# Witch.net
KiCad netlist of a schematic drawn in EAGLE
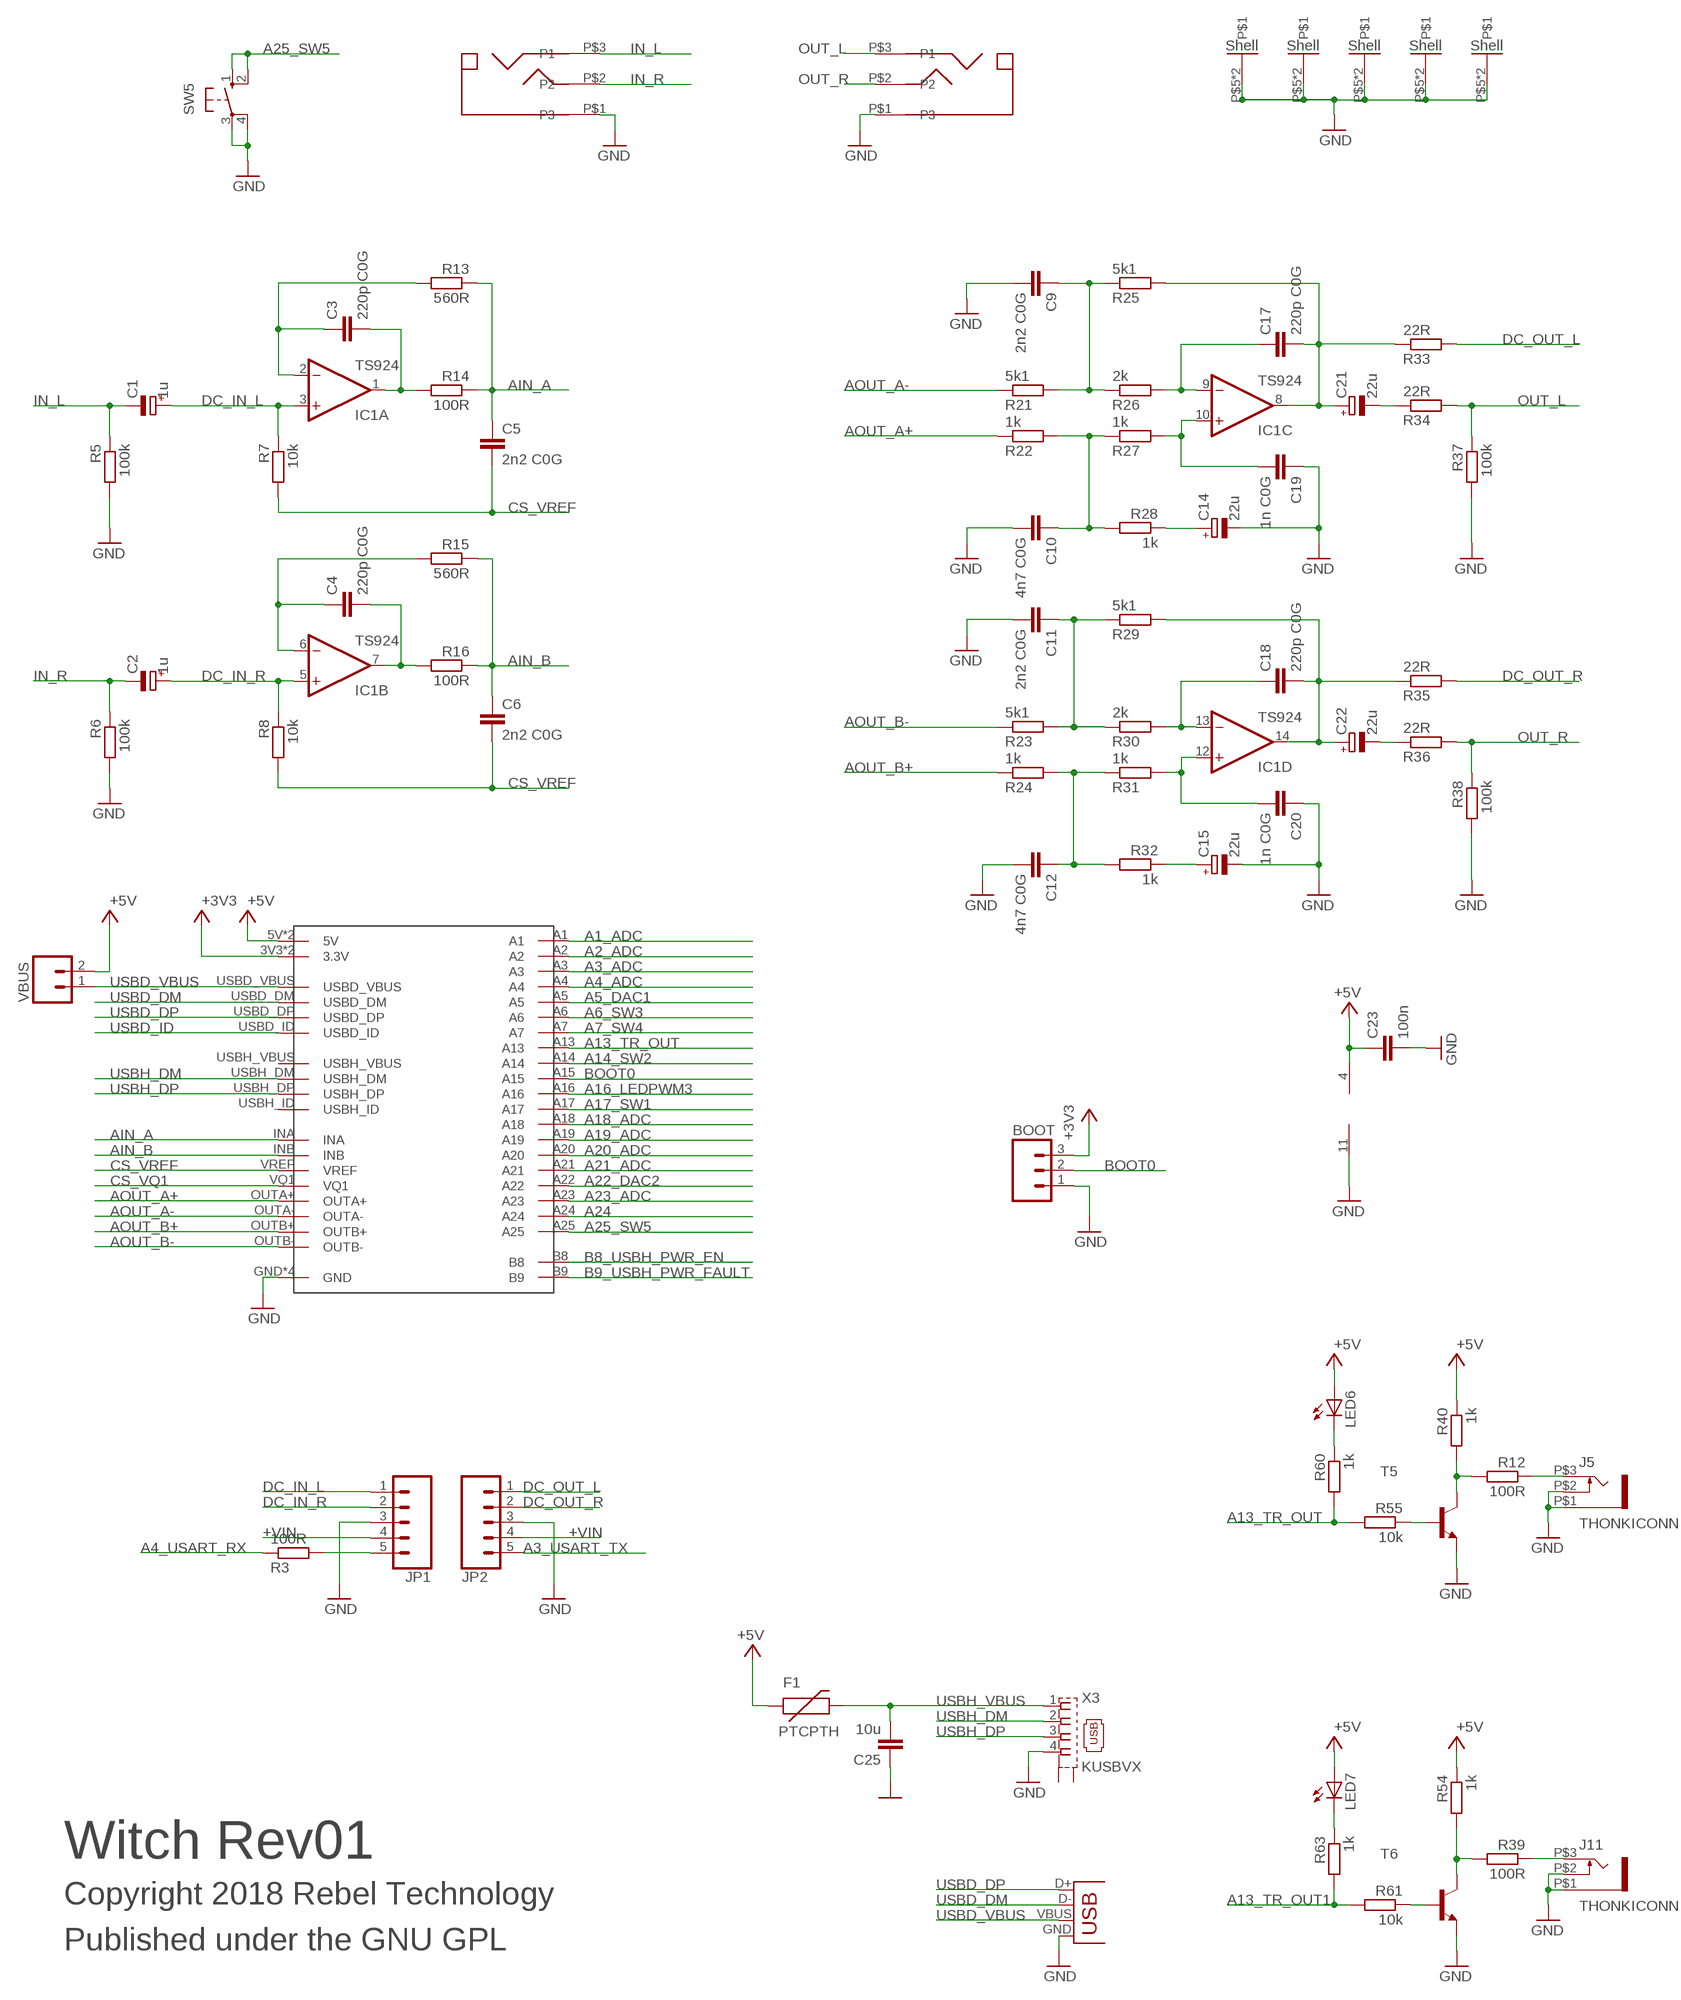
[diagram p0: schematic, sheet 1, part 1 of 2]
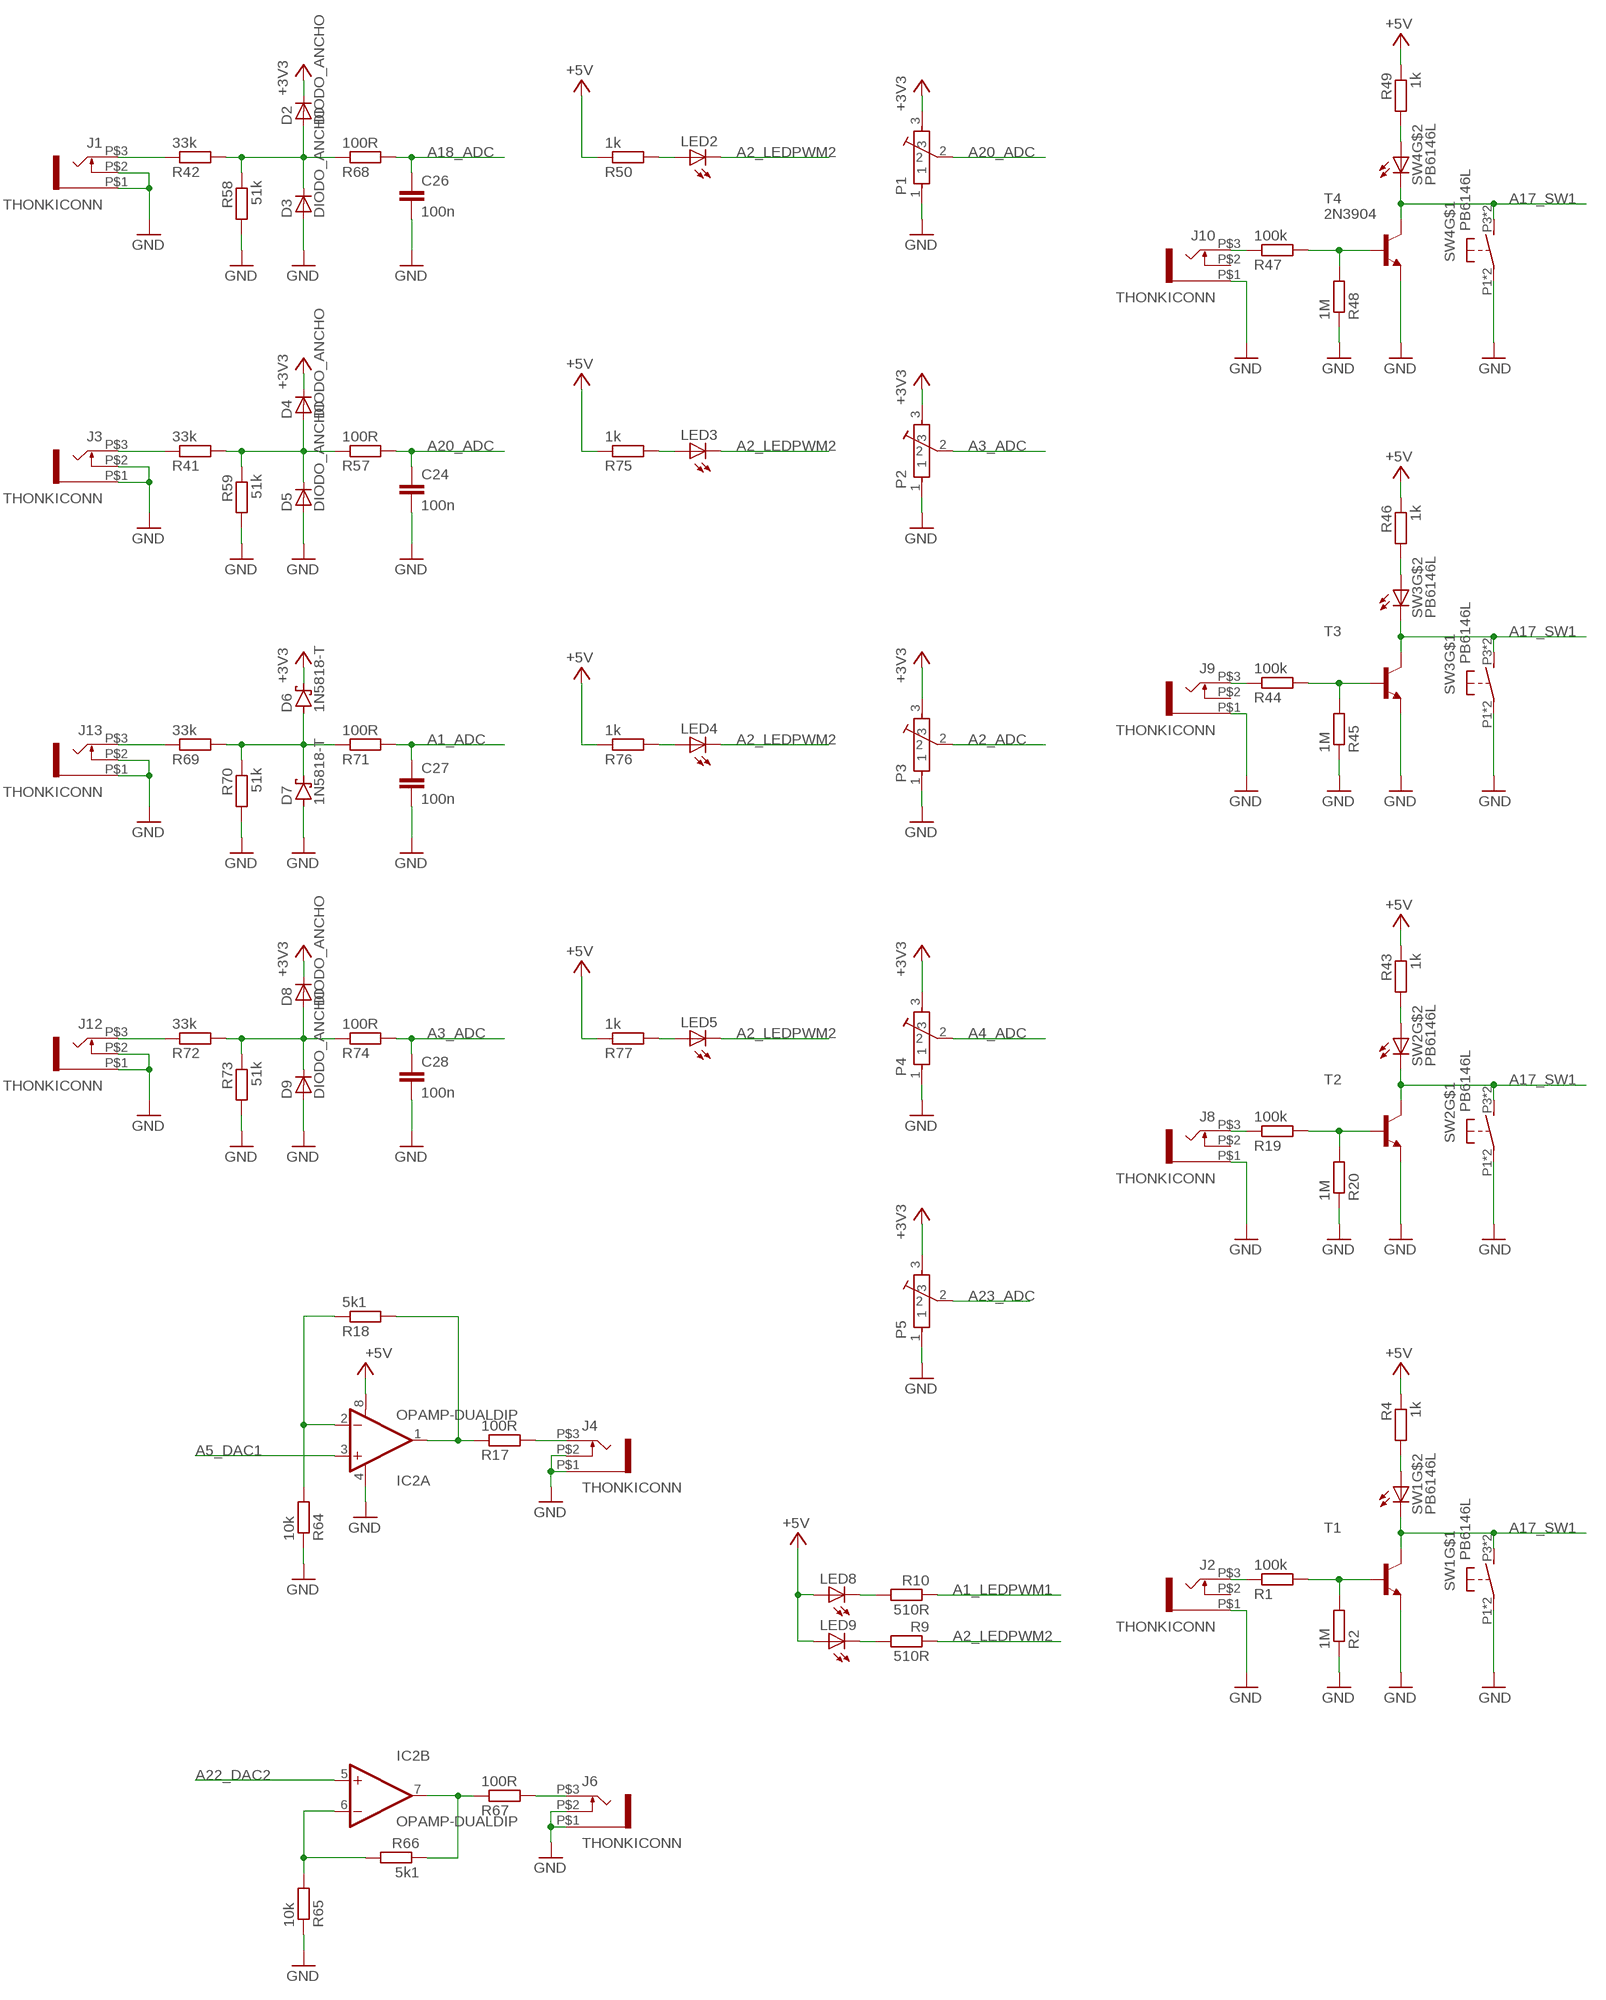
[diagram p1: schematic, sheet 1, part 2 of 2]

(export (version "E")
  (design (tool "Eeschema 10.0.6"))
  (components
    (comp (ref "BOOT")
      (value "M03PTH")
      (footprint "eagle-import:1X03")
      (libsource (lib "eagle-import") (part "M03PTH"))
    )
    (comp (ref "C1")
      (value "1u")
      (footprint "eagle-import:E1,8-4")
      (libsource (lib "eagle-import") (part "CPOL-EUE1.8-4"))
    )
    (comp (ref "C2")
      (value "1u")
      (footprint "eagle-import:E1,8-4")
      (libsource (lib "eagle-import") (part "CPOL-EUE1.8-4"))
    )
    (comp (ref "C3")
      (value "220p C0G")
      (footprint "eagle-import:C050-025X075")
      (libsource (lib "eagle-import") (part "C-EU050-025X075"))
    )
    (comp (ref "C4")
      (value "220p C0G")
      (footprint "eagle-import:C050-025X075")
      (libsource (lib "eagle-import") (part "C-EU050-025X075"))
    )
    (comp (ref "C5")
      (value "2n2 C0G")
      (footprint "eagle-import:C050-025X075")
      (libsource (lib "eagle-import") (part "C-EU050-025X075"))
    )
    (comp (ref "C6")
      (value "2n2 C0G")
      (footprint "eagle-import:C050-025X075")
      (libsource (lib "eagle-import") (part "C-EU050-025X075"))
    )
    (comp (ref "C9")
      (value "2n2 C0G")
      (footprint "eagle-import:C050-025X075")
      (libsource (lib "eagle-import") (part "C-EU050-025X075"))
    )
    (comp (ref "C10")
      (value "4n7 C0G")
      (footprint "eagle-import:C050-025X075")
      (libsource (lib "eagle-import") (part "C-EU050-025X075"))
    )
    (comp (ref "C11")
      (value "2n2 C0G")
      (footprint "eagle-import:C050-025X075")
      (libsource (lib "eagle-import") (part "C-EU050-025X075"))
    )
    (comp (ref "C12")
      (value "4n7 C0G")
      (footprint "eagle-import:C050-025X075")
      (libsource (lib "eagle-import") (part "C-EU050-025X075"))
    )
    (comp (ref "C14")
      (value "22u")
      (footprint "eagle-import:E1,8-4")
      (libsource (lib "eagle-import") (part "CPOL-EUE1.8-4"))
    )
    (comp (ref "C15")
      (value "22u")
      (footprint "eagle-import:E1,8-4")
      (libsource (lib "eagle-import") (part "CPOL-EUE1.8-4"))
    )
    (comp (ref "C17")
      (value "220p C0G")
      (footprint "eagle-import:C050-025X075")
      (libsource (lib "eagle-import") (part "C-EU050-025X075"))
    )
    (comp (ref "C18")
      (value "220p C0G")
      (footprint "eagle-import:C050-025X075")
      (libsource (lib "eagle-import") (part "C-EU050-025X075"))
    )
    (comp (ref "C19")
      (value "1n C0G")
      (footprint "eagle-import:C050-025X075")
      (libsource (lib "eagle-import") (part "C-EU050-025X075"))
    )
    (comp (ref "C20")
      (value "1n C0G")
      (footprint "eagle-import:C050-025X075")
      (libsource (lib "eagle-import") (part "C-EU050-025X075"))
    )
    (comp (ref "C21")
      (value "22u")
      (footprint "eagle-import:E1,8-4")
      (libsource (lib "eagle-import") (part "CPOL-EUE1.8-4"))
    )
    (comp (ref "C22")
      (value "22u")
      (footprint "eagle-import:E1,8-4")
      (libsource (lib "eagle-import") (part "CPOL-EUE1.8-4"))
    )
    (comp (ref "C23")
      (value "100n")
      (footprint "eagle-import:C050-025X075")
      (libsource (lib "eagle-import") (part "C-EU050-025X075"))
    )
    (comp (ref "C24")
      (value "100n")
      (footprint "eagle-import:C050-025X075")
      (libsource (lib "eagle-import") (part "C-EU050-025X075"))
    )
    (comp (ref "C25")
      (value "10u")
      (footprint "eagle-import:C050-025X075")
      (libsource (lib "eagle-import") (part "C-EU050-025X075"))
    )
    (comp (ref "C26")
      (value "100n")
      (footprint "eagle-import:C050-025X075")
      (libsource (lib "eagle-import") (part "C-EU050-025X075"))
    )
    (comp (ref "C27")
      (value "100n")
      (footprint "eagle-import:C050-025X075")
      (libsource (lib "eagle-import") (part "C-EU050-025X075"))
    )
    (comp (ref "C28")
      (value "100n")
      (footprint "eagle-import:C050-025X075")
      (libsource (lib "eagle-import") (part "C-EU050-025X075"))
    )
    (comp (ref "D2")
      (value "DIODO_ANCHO")
      (footprint "eagle-import:D-5.2")
      (libsource (lib "eagle-import") (part "DIODO_ANCHO"))
    )
    (comp (ref "D3")
      (value "DIODO_ANCHO")
      (footprint "eagle-import:D-5.2")
      (libsource (lib "eagle-import") (part "DIODO_ANCHO"))
    )
    (comp (ref "D4")
      (value "DIODO_ANCHO")
      (footprint "eagle-import:D-5.2")
      (libsource (lib "eagle-import") (part "DIODO_ANCHO"))
    )
    (comp (ref "D5")
      (value "DIODO_ANCHO")
      (footprint "eagle-import:D-5.2")
      (libsource (lib "eagle-import") (part "DIODO_ANCHO"))
    )
    (comp (ref "D6")
      (value "1N5818-T")
      (footprint "eagle-import:DO41-7.6")
      (libsource (lib "eagle-import") (part "1N5818-T"))
    )
    (comp (ref "D7")
      (value "1N5818-T")
      (footprint "eagle-import:DO41-7.6")
      (libsource (lib "eagle-import") (part "1N5818-T"))
    )
    (comp (ref "D8")
      (value "DIODO_ANCHO")
      (footprint "eagle-import:D-5.2")
      (libsource (lib "eagle-import") (part "DIODO_ANCHO"))
    )
    (comp (ref "D9")
      (value "DIODO_ANCHO")
      (footprint "eagle-import:D-5.2")
      (libsource (lib "eagle-import") (part "DIODO_ANCHO"))
    )
    (comp (ref "F1")
      (value "PTCPTH")
      (footprint "eagle-import:PTC")
      (libsource (lib "eagle-import") (part "PTCPTH"))
    )
    (comp (ref "IC1")
      (value "TS924")
      (footprint "eagle-import:DIL14")
      (libsource (lib "eagle-import") (part "LM324N"))
    )
    (comp (ref "IC2")
      (value "OPAMP-DUALDIP")
      (footprint "eagle-import:DIP08")
      (libsource (lib "eagle-import") (part "OPAMP-DUALDIP"))
    )
    (comp (ref "J1")
      (value "THONKICONN")
      (footprint "eagle-import:THONKICONN")
      (libsource (lib "eagle-import") (part "THONKICONN"))
    )
    (comp (ref "J2")
      (value "THONKICONN")
      (footprint "eagle-import:THONKICONN")
      (libsource (lib "eagle-import") (part "THONKICONN"))
    )
    (comp (ref "J3")
      (value "THONKICONN")
      (footprint "eagle-import:THONKICONN")
      (libsource (lib "eagle-import") (part "THONKICONN"))
    )
    (comp (ref "J4")
      (value "THONKICONN")
      (footprint "eagle-import:THONKICONN")
      (libsource (lib "eagle-import") (part "THONKICONN"))
    )
    (comp (ref "J5")
      (value "THONKICONN")
      (footprint "eagle-import:THONKICONN")
      (libsource (lib "eagle-import") (part "THONKICONN"))
    )
    (comp (ref "J6")
      (value "THONKICONN")
      (footprint "eagle-import:THONKICONN")
      (libsource (lib "eagle-import") (part "THONKICONN"))
    )
    (comp (ref "J8")
      (value "THONKICONN")
      (footprint "eagle-import:THONKICONN")
      (libsource (lib "eagle-import") (part "THONKICONN"))
    )
    (comp (ref "J9")
      (value "THONKICONN")
      (footprint "eagle-import:THONKICONN")
      (libsource (lib "eagle-import") (part "THONKICONN"))
    )
    (comp (ref "J10")
      (value "THONKICONN")
      (footprint "eagle-import:THONKICONN")
      (libsource (lib "eagle-import") (part "THONKICONN"))
    )
    (comp (ref "J11")
      (value "THONKICONN")
      (footprint "eagle-import:THONKICONN")
      (libsource (lib "eagle-import") (part "THONKICONN"))
    )
    (comp (ref "J12")
      (value "THONKICONN")
      (footprint "eagle-import:THONKICONN")
      (libsource (lib "eagle-import") (part "THONKICONN"))
    )
    (comp (ref "J13")
      (value "THONKICONN")
      (footprint "eagle-import:THONKICONN")
      (libsource (lib "eagle-import") (part "THONKICONN"))
    )
    (comp (ref "JP1")
      (value "CONN_05JST-VERT")
      (footprint "eagle-import:JST-5-PTH-VERT")
      (libsource (lib "eagle-import") (part "CONN_05JST-VERT"))
    )
    (comp (ref "JP2")
      (value "CONN_05JST-VERT")
      (footprint "eagle-import:JST-5-PTH-VERT")
      (libsource (lib "eagle-import") (part "CONN_05JST-VERT"))
    )
    (comp (ref "LED2")
      (value "LED3MM")
      (footprint "eagle-import:LED3MM")
      (libsource (lib "eagle-import") (part "LED3MM"))
    )
    (comp (ref "LED3")
      (value "LED3MM")
      (footprint "eagle-import:LED3MM")
      (libsource (lib "eagle-import") (part "LED3MM"))
    )
    (comp (ref "LED4")
      (value "LED3MM")
      (footprint "eagle-import:LED3MM")
      (libsource (lib "eagle-import") (part "LED3MM"))
    )
    (comp (ref "LED5")
      (value "LED3MM")
      (footprint "eagle-import:LED3MM")
      (libsource (lib "eagle-import") (part "LED3MM"))
    )
    (comp (ref "LED6")
      (value "LED3MM")
      (footprint "eagle-import:LED3MM")
      (libsource (lib "eagle-import") (part "LED3MM"))
    )
    (comp (ref "LED7")
      (value "LED3MM")
      (footprint "eagle-import:LED3MM")
      (libsource (lib "eagle-import") (part "LED3MM"))
    )
    (comp (ref "LED8")
      (value "LED3MM")
      (footprint "eagle-import:LED3MM")
      (libsource (lib "eagle-import") (part "LED3MM"))
    )
    (comp (ref "LED9")
      (value "LED3MM")
      (footprint "eagle-import:LED3MM")
      (libsource (lib "eagle-import") (part "LED3MM"))
    )
    (comp (ref "P1")
      (value "POT-ALPS-RK09L1140")
      (footprint "eagle-import:POT-ALPS-RK09L1140")
      (libsource (lib "eagle-import") (part "POT-ALPS-RK09L1140"))
    )
    (comp (ref "P2")
      (value "POT-ALPS-RK09L1140")
      (footprint "eagle-import:POT-ALPS-RK09L1140")
      (libsource (lib "eagle-import") (part "POT-ALPS-RK09L1140"))
    )
    (comp (ref "P3")
      (value "POT-ALPS-RK09L1140")
      (footprint "eagle-import:POT-ALPS-RK09L1140")
      (libsource (lib "eagle-import") (part "POT-ALPS-RK09L1140"))
    )
    (comp (ref "P4")
      (value "POT-ALPS-RK09L1140")
      (footprint "eagle-import:POT-ALPS-RK09L1140")
      (libsource (lib "eagle-import") (part "POT-ALPS-RK09L1140"))
    )
    (comp (ref "P5")
      (value "POT-ALPS-RK09L1140")
      (footprint "eagle-import:POT-ALPS-RK09L1140")
      (libsource (lib "eagle-import") (part "POT-ALPS-RK09L1140"))
    )
    (comp (ref "R1")
      (value "100k")
      (footprint "eagle-import:0204_5")
      (libsource (lib "eagle-import") (part "R-EU_0204/5"))
    )
    (comp (ref "R2")
      (value "1M")
      (footprint "eagle-import:0204_5")
      (libsource (lib "eagle-import") (part "R-EU_0204/5"))
    )
    (comp (ref "R3")
      (value "100R")
      (footprint "eagle-import:0204_5")
      (libsource (lib "eagle-import") (part "R-EU_0204/5"))
    )
    (comp (ref "R4")
      (value "1k")
      (footprint "eagle-import:0204_5")
      (libsource (lib "eagle-import") (part "R-EU_0204/5"))
    )
    (comp (ref "R5")
      (value "100k")
      (footprint "eagle-import:0204_5")
      (libsource (lib "eagle-import") (part "R-EU_0204/5"))
    )
    (comp (ref "R6")
      (value "100k")
      (footprint "eagle-import:0204_5")
      (libsource (lib "eagle-import") (part "R-EU_0204/5"))
    )
    (comp (ref "R7")
      (value "10k")
      (footprint "eagle-import:0204_5")
      (libsource (lib "eagle-import") (part "R-EU_0204/5"))
    )
    (comp (ref "R8")
      (value "10k")
      (footprint "eagle-import:0204_5")
      (libsource (lib "eagle-import") (part "R-EU_0204/5"))
    )
    (comp (ref "R9")
      (value "510R")
      (footprint "eagle-import:0204_5")
      (libsource (lib "eagle-import") (part "R-EU_0204/5"))
    )
    (comp (ref "R10")
      (value "510R")
      (footprint "eagle-import:0204_5")
      (libsource (lib "eagle-import") (part "R-EU_0204/5"))
    )
    (comp (ref "R12")
      (value "100R")
      (footprint "eagle-import:0204_5")
      (libsource (lib "eagle-import") (part "R-EU_0204/5"))
    )
    (comp (ref "R13")
      (value "560R")
      (footprint "eagle-import:0204_5")
      (libsource (lib "eagle-import") (part "R-EU_0204/5"))
    )
    (comp (ref "R14")
      (value "100R")
      (footprint "eagle-import:0204_5")
      (libsource (lib "eagle-import") (part "R-EU_0204/5"))
    )
    (comp (ref "R15")
      (value "560R")
      (footprint "eagle-import:0204_5")
      (libsource (lib "eagle-import") (part "R-EU_0204/5"))
    )
    (comp (ref "R16")
      (value "100R")
      (footprint "eagle-import:0204_5")
      (libsource (lib "eagle-import") (part "R-EU_0204/5"))
    )
    (comp (ref "R17")
      (value "100R")
      (footprint "eagle-import:0204_5")
      (libsource (lib "eagle-import") (part "R-EU_0204/5"))
    )
    (comp (ref "R18")
      (value "5k1")
      (footprint "eagle-import:0204_5")
      (libsource (lib "eagle-import") (part "R-EU_0204/5"))
    )
    (comp (ref "R19")
      (value "100k")
      (footprint "eagle-import:0204_5")
      (libsource (lib "eagle-import") (part "R-EU_0204/5"))
    )
    (comp (ref "R20")
      (value "1M")
      (footprint "eagle-import:0204_7")
      (libsource (lib "eagle-import") (part "R-EU_0204/7"))
    )
    (comp (ref "R21")
      (value "5k1")
      (footprint "eagle-import:0204_5")
      (libsource (lib "eagle-import") (part "R-EU_0204/5"))
    )
    (comp (ref "R22")
      (value "1k")
      (footprint "eagle-import:0204_5")
      (libsource (lib "eagle-import") (part "R-EU_0204/5"))
    )
    (comp (ref "R23")
      (value "5k1")
      (footprint "eagle-import:0204_5")
      (libsource (lib "eagle-import") (part "R-EU_0204/5"))
    )
    (comp (ref "R24")
      (value "1k")
      (footprint "eagle-import:0204_5")
      (libsource (lib "eagle-import") (part "R-EU_0204/5"))
    )
    (comp (ref "R25")
      (value "5k1")
      (footprint "eagle-import:0204_5")
      (libsource (lib "eagle-import") (part "R-EU_0204/5"))
    )
    (comp (ref "R26")
      (value "2k")
      (footprint "eagle-import:0204_5")
      (libsource (lib "eagle-import") (part "R-EU_0204/5"))
    )
    (comp (ref "R27")
      (value "1k")
      (footprint "eagle-import:0204_5")
      (libsource (lib "eagle-import") (part "R-EU_0204/5"))
    )
    (comp (ref "R28")
      (value "1k")
      (footprint "eagle-import:0204_5")
      (libsource (lib "eagle-import") (part "R-EU_0204/5"))
    )
    (comp (ref "R29")
      (value "5k1")
      (footprint "eagle-import:0204_5")
      (libsource (lib "eagle-import") (part "R-EU_0204/5"))
    )
    (comp (ref "R30")
      (value "2k")
      (footprint "eagle-import:0204_5")
      (libsource (lib "eagle-import") (part "R-EU_0204/5"))
    )
    (comp (ref "R31")
      (value "1k")
      (footprint "eagle-import:0204_5")
      (libsource (lib "eagle-import") (part "R-EU_0204/5"))
    )
    (comp (ref "R32")
      (value "1k")
      (footprint "eagle-import:0204_5")
      (libsource (lib "eagle-import") (part "R-EU_0204/5"))
    )
    (comp (ref "R33")
      (value "22R")
      (footprint "eagle-import:0204_5")
      (libsource (lib "eagle-import") (part "R-EU_0204/5"))
    )
    (comp (ref "R34")
      (value "22R")
      (footprint "eagle-import:0204_5")
      (libsource (lib "eagle-import") (part "R-EU_0204/5"))
    )
    (comp (ref "R35")
      (value "22R")
      (footprint "eagle-import:0204_5")
      (libsource (lib "eagle-import") (part "R-EU_0204/5"))
    )
    (comp (ref "R36")
      (value "22R")
      (footprint "eagle-import:0204_5")
      (libsource (lib "eagle-import") (part "R-EU_0204/5"))
    )
    (comp (ref "R37")
      (value "100k")
      (footprint "eagle-import:0204_5")
      (libsource (lib "eagle-import") (part "R-EU_0204/5"))
    )
    (comp (ref "R38")
      (value "100k")
      (footprint "eagle-import:0204_5")
      (libsource (lib "eagle-import") (part "R-EU_0204/5"))
    )
    (comp (ref "R39")
      (value "100R")
      (footprint "eagle-import:0204_5")
      (libsource (lib "eagle-import") (part "R-EU_0204/5"))
    )
    (comp (ref "R40")
      (value "1k")
      (footprint "eagle-import:0204_5")
      (libsource (lib "eagle-import") (part "R-EU_0204/5"))
    )
    (comp (ref "R41")
      (value "33k")
      (footprint "eagle-import:0204_5")
      (libsource (lib "eagle-import") (part "R-EU_0204/5"))
    )
    (comp (ref "R42")
      (value "33k")
      (footprint "eagle-import:0204_5")
      (libsource (lib "eagle-import") (part "R-EU_0204/5"))
    )
    (comp (ref "R43")
      (value "1k")
      (footprint "eagle-import:0204_5")
      (libsource (lib "eagle-import") (part "R-EU_0204/5"))
    )
    (comp (ref "R44")
      (value "100k")
      (footprint "eagle-import:0204_5")
      (libsource (lib "eagle-import") (part "R-EU_0204/5"))
    )
    (comp (ref "R45")
      (value "1M")
      (footprint "eagle-import:0204_5")
      (libsource (lib "eagle-import") (part "R-EU_0204/5"))
    )
    (comp (ref "R46")
      (value "1k")
      (footprint "eagle-import:0204_5")
      (libsource (lib "eagle-import") (part "R-EU_0204/5"))
    )
    (comp (ref "R47")
      (value "100k")
      (footprint "eagle-import:0204_5")
      (libsource (lib "eagle-import") (part "R-EU_0204/5"))
    )
    (comp (ref "R48")
      (value "1M")
      (footprint "eagle-import:0204_5")
      (libsource (lib "eagle-import") (part "R-EU_0204/5"))
    )
    (comp (ref "R49")
      (value "1k")
      (footprint "eagle-import:0204_5")
      (libsource (lib "eagle-import") (part "R-EU_0204/5"))
    )
    (comp (ref "R50")
      (value "1k")
      (footprint "eagle-import:0204_5")
      (libsource (lib "eagle-import") (part "R-EU_0204/5"))
    )
    (comp (ref "R54")
      (value "1k")
      (footprint "eagle-import:0204_5")
      (libsource (lib "eagle-import") (part "R-EU_0204/5"))
    )
    (comp (ref "R55")
      (value "10k")
      (footprint "eagle-import:0204_5")
      (libsource (lib "eagle-import") (part "R-EU_0204/5"))
    )
    (comp (ref "R57")
      (value "100R")
      (footprint "eagle-import:0204_5")
      (libsource (lib "eagle-import") (part "R-EU_0204/5"))
    )
    (comp (ref "R58")
      (value "51k")
      (footprint "eagle-import:0204_5")
      (libsource (lib "eagle-import") (part "R-EU_0204/5"))
    )
    (comp (ref "R59")
      (value "51k")
      (footprint "eagle-import:0204_5")
      (libsource (lib "eagle-import") (part "R-EU_0204/5"))
    )
    (comp (ref "R60")
      (value "1k")
      (footprint "eagle-import:0204_5")
      (libsource (lib "eagle-import") (part "R-EU_0204/5"))
    )
    (comp (ref "R61")
      (value "10k")
      (footprint "eagle-import:0204_5")
      (libsource (lib "eagle-import") (part "R-EU_0204/5"))
    )
    (comp (ref "R63")
      (value "1k")
      (footprint "eagle-import:0204_5")
      (libsource (lib "eagle-import") (part "R-EU_0204/5"))
    )
    (comp (ref "R64")
      (value "10k")
      (footprint "eagle-import:0204_5")
      (libsource (lib "eagle-import") (part "R-EU_0204/5"))
    )
    (comp (ref "R65")
      (value "10k")
      (footprint "eagle-import:0204_5")
      (libsource (lib "eagle-import") (part "R-EU_0204/5"))
    )
    (comp (ref "R66")
      (value "5k1")
      (footprint "eagle-import:0204_5")
      (libsource (lib "eagle-import") (part "R-EU_0204/5"))
    )
    (comp (ref "R67")
      (value "100R")
      (footprint "eagle-import:0204_5")
      (libsource (lib "eagle-import") (part "R-EU_0204/5"))
    )
    (comp (ref "R68")
      (value "100R")
      (footprint "eagle-import:0204_5")
      (libsource (lib "eagle-import") (part "R-EU_0204/5"))
    )
    (comp (ref "R69")
      (value "33k")
      (footprint "eagle-import:0204_5")
      (libsource (lib "eagle-import") (part "R-EU_0204/5"))
    )
    (comp (ref "R70")
      (value "51k")
      (footprint "eagle-import:0204_5")
      (libsource (lib "eagle-import") (part "R-EU_0204/5"))
    )
    (comp (ref "R71")
      (value "100R")
      (footprint "eagle-import:0204_5")
      (libsource (lib "eagle-import") (part "R-EU_0204/5"))
    )
    (comp (ref "R72")
      (value "33k")
      (footprint "eagle-import:0204_5")
      (libsource (lib "eagle-import") (part "R-EU_0204/5"))
    )
    (comp (ref "R73")
      (value "51k")
      (footprint "eagle-import:0204_5")
      (libsource (lib "eagle-import") (part "R-EU_0204/5"))
    )
    (comp (ref "R74")
      (value "100R")
      (footprint "eagle-import:0204_5")
      (libsource (lib "eagle-import") (part "R-EU_0204/5"))
    )
    (comp (ref "R75")
      (value "1k")
      (footprint "eagle-import:0204_5")
      (libsource (lib "eagle-import") (part "R-EU_0204/5"))
    )
    (comp (ref "R76")
      (value "1k")
      (footprint "eagle-import:0204_5")
      (libsource (lib "eagle-import") (part "R-EU_0204/5"))
    )
    (comp (ref "R77")
      (value "1k")
      (footprint "eagle-import:0204_5")
      (libsource (lib "eagle-import") (part "R-EU_0204/5"))
    )
    (comp (ref "SW1")
      (value "PB6146L")
      (footprint "eagle-import:PB6146L")
      (libsource (lib "eagle-import") (part "PB6146L"))
    )
    (comp (ref "SW2")
      (value "PB6146L")
      (footprint "eagle-import:PB6146L")
      (libsource (lib "eagle-import") (part "PB6146L"))
    )
    (comp (ref "SW3")
      (value "PB6146L")
      (footprint "eagle-import:PB6146L")
      (libsource (lib "eagle-import") (part "PB6146L"))
    )
    (comp (ref "SW4")
      (value "PB6146L")
      (footprint "eagle-import:PB6146L")
      (libsource (lib "eagle-import") (part "PB6146L"))
    )
    (comp (ref "SW5")
      (value "10-XX")
      (footprint "eagle-import:B3F-10XX")
      (fields (field (name "MPN") "B3F-1000"))
      (libsource (lib "eagle-import") (part "10-XX"))
    )
    (comp (ref "T1")
      (value "2N3904-NPN-TO92-EBC")
      (footprint "eagle-import:TO92-EBC")
      (libsource (lib "eagle-import") (part "-NPN-TO92-EBC2N3904"))
    )
    (comp (ref "T2")
      (value "2N3904-NPN-TO92-EBC")
      (footprint "eagle-import:TO92-EBC")
      (libsource (lib "eagle-import") (part "-NPN-TO92-EBC2N3904"))
    )
    (comp (ref "T3")
      (value "2N3904-NPN-TO92-EBC")
      (footprint "eagle-import:TO92-EBC")
      (libsource (lib "eagle-import") (part "-NPN-TO92-EBC2N3904"))
    )
    (comp (ref "T4")
      (value "2N3904")
      (footprint "eagle-import:TO92")
      (libsource (lib "eagle-import") (part "2N3904"))
    )
    (comp (ref "T5")
      (value "2N3904-NPN-TO92-EBC")
      (footprint "eagle-import:TO92-EBC")
      (libsource (lib "eagle-import") (part "-NPN-TO92-EBC2N3904"))
    )
    (comp (ref "T6")
      (value "2N3904-NPN-TO92-EBC")
      (footprint "eagle-import:TO92-EBC")
      (libsource (lib "eagle-import") (part "-NPN-TO92-EBC2N3904"))
    )
    (comp (ref "U$4")
      (value "THONKICONN_STEREO")
      (footprint "eagle-import:THONKICONN_STEREO")
      (libsource (lib "eagle-import") (part "THONKICONN_STEREO"))
    )
    (comp (ref "U$5")
      (value "THONKICONN_STEREO")
      (footprint "eagle-import:THONKICONN_STEREO")
      (libsource (lib "eagle-import") (part "THONKICONN_STEREO"))
    )
    (comp (ref "U$10")
      (value "OWL_DIGITAL_LITE_2USB")
      (footprint "eagle-import:OWL_DIGITAL_LITE_2USB")
      (libsource (lib "eagle-import") (part "OWL_DIGITAL_LITE_2USB"))
    )
    (comp (ref "VBUS")
      (value "M02PTH")
      (footprint "eagle-import:1X02")
      (libsource (lib "eagle-import") (part "M02PTH"))
    )
    (comp (ref "X3")
      (value "KUSBVX")
      (footprint "eagle-import:KUSBVX")
      (libsource (lib "eagle-import") (part "KUSBVX"))
    )
    (comp (ref "X5")
      (value "USBPTH-VERTICAL")
      (footprint "eagle-import:USB-B-PTH-VERTICAL")
      (libsource (lib "eagle-import") (part "USBPTH-VERTICAL"))
    )
  )
  (nets
    (net (code "1") (name "+3V3") (class "Default")
      (node (ref "BOOT") (pin "3") (pinfunction "3_3") (pintype "passive"))
      (node (ref "D2") (pin "C") (pinfunction "C_C") (pintype "passive"))
      (node (ref "D4") (pin "C") (pinfunction "C_C") (pintype "passive"))
      (node (ref "D6") (pin "C") (pinfunction "C_C") (pintype "passive"))
      (node (ref "D8") (pin "C") (pinfunction "C_C") (pintype "passive"))
      (node (ref "P1") (pin "3") (pinfunction "3_3") (pintype "bidirectional"))
      (node (ref "P2") (pin "3") (pinfunction "3_3") (pintype "bidirectional"))
      (node (ref "P3") (pin "3") (pinfunction "3_3") (pintype "bidirectional"))
      (node (ref "P4") (pin "3") (pinfunction "3_3") (pintype "bidirectional"))
      (node (ref "P5") (pin "3") (pinfunction "3_3") (pintype "bidirectional"))
      (node (ref "U$10") (pin "3V3") (pinfunction "3.3V_3V3") (pintype "bidirectional"))
      (node (ref "U$10") (pin "3V3_2") (pinfunction "3.3V_3V3_2") (pintype "bidirectional"))
    )
    (net (code "2") (name "+5V") (class "Default")
      (node (ref "C23") (pin "1") (pinfunction "1_1") (pintype "passive"))
      (node (ref "F1") (pin "P$1") (pinfunction "1_P$1") (pintype "bidirectional"))
      (node (ref "IC1") (pin "4") (pinfunction "V+_4") (pintype "power_in"))
      (node (ref "IC2") (pin "8") (pinfunction "V+_8") (pintype "power_in"))
      (node (ref "LED6") (pin "A") (pinfunction "A_A") (pintype "passive"))
      (node (ref "LED7") (pin "A") (pinfunction "A_A") (pintype "passive"))
      (node (ref "LED8") (pin "A") (pinfunction "A_A") (pintype "passive"))
      (node (ref "LED9") (pin "A") (pinfunction "A_A") (pintype "passive"))
      (node (ref "R4") (pin "1") (pinfunction "1_1") (pintype "passive"))
      (node (ref "R40") (pin "1") (pinfunction "1_1") (pintype "passive"))
      (node (ref "R43") (pin "1") (pinfunction "1_1") (pintype "passive"))
      (node (ref "R46") (pin "1") (pinfunction "1_1") (pintype "passive"))
      (node (ref "R49") (pin "1") (pinfunction "1_1") (pintype "passive"))
      (node (ref "R50") (pin "1") (pinfunction "1_1") (pintype "passive"))
      (node (ref "R54") (pin "1") (pinfunction "1_1") (pintype "passive"))
      (node (ref "R75") (pin "1") (pinfunction "1_1") (pintype "passive"))
      (node (ref "R76") (pin "1") (pinfunction "1_1") (pintype "passive"))
      (node (ref "R77") (pin "1") (pinfunction "1_1") (pintype "passive"))
      (node (ref "U$10") (pin "5V") (pinfunction "5V_5V") (pintype "bidirectional"))
      (node (ref "U$10") (pin "5V_2") (pinfunction "5V_5V_2") (pintype "bidirectional"))
      (node (ref "VBUS") (pin "2") (pinfunction "2_2") (pintype "passive"))
    )
    (net (code "3") (name "/+VIN") (class "Default")
      (node (ref "JP1") (pin "4") (pinfunction "4_4") (pintype "passive"))
      (node (ref "JP2") (pin "4") (pinfunction "4_4") (pintype "passive"))
    )
    (net (code "4") (name "/A1_ADC") (class "Default")
      (node (ref "C27") (pin "1") (pinfunction "1_1") (pintype "passive"))
      (node (ref "R71") (pin "2") (pinfunction "2_2") (pintype "passive"))
      (node (ref "U$10") (pin "A1") (pinfunction "A1_A1") (pintype "bidirectional"))
    )
    (net (code "5") (name "/A1_LEDPWM1") (class "Default")
      (node (ref "R10") (pin "1") (pinfunction "1_1") (pintype "passive"))
    )
    (net (code "6") (name "/A2_ADC") (class "Default")
      (node (ref "P3") (pin "2") (pinfunction "2_2") (pintype "bidirectional"))
      (node (ref "U$10") (pin "A2") (pinfunction "A2_A2") (pintype "bidirectional"))
    )
    (net (code "7") (name "/A2_LEDPWM2") (class "Default")
      (node (ref "LED2") (pin "K") (pinfunction "C_K") (pintype "passive"))
      (node (ref "LED3") (pin "K") (pinfunction "C_K") (pintype "passive"))
      (node (ref "LED4") (pin "K") (pinfunction "C_K") (pintype "passive"))
      (node (ref "LED5") (pin "K") (pinfunction "C_K") (pintype "passive"))
      (node (ref "R9") (pin "1") (pinfunction "1_1") (pintype "passive"))
    )
    (net (code "8") (name "/A3_ADC") (class "Default")
      (node (ref "C28") (pin "1") (pinfunction "1_1") (pintype "passive"))
      (node (ref "R74") (pin "2") (pinfunction "2_2") (pintype "passive"))
      (node (ref "U$10") (pin "A3") (pinfunction "A3_A3") (pintype "bidirectional"))
    )
    (net (code "9") (name "/A3_USART_TX") (class "Default")
      (node (ref "JP2") (pin "5") (pinfunction "5_5") (pintype "passive"))
    )
    (net (code "10") (name "/A4_ADC") (class "Default")
      (node (ref "P4") (pin "2") (pinfunction "2_2") (pintype "bidirectional"))
      (node (ref "U$10") (pin "A4") (pinfunction "A4_A4") (pintype "bidirectional"))
    )
    (net (code "11") (name "/A4_USART_RX") (class "Default")
      (node (ref "R3") (pin "1") (pinfunction "1_1") (pintype "passive"))
    )
    (net (code "12") (name "/A5_DAC1") (class "Default")
      (node (ref "IC2") (pin "3") (pinfunction "+IN_3") (pintype "input"))
      (node (ref "U$10") (pin "A5") (pinfunction "A5_A5") (pintype "bidirectional"))
    )
    (net (code "13") (name "/A6_SW3") (class "Default")
      (node (ref "U$10") (pin "A6") (pinfunction "A6_A6") (pintype "bidirectional"))
    )
    (net (code "14") (name "/A7_SW4") (class "Default")
      (node (ref "U$10") (pin "A7") (pinfunction "A7_A7") (pintype "bidirectional"))
    )
    (net (code "15") (name "/A13_TR_OUT") (class "Default")
      (node (ref "R55") (pin "2") (pinfunction "2_2") (pintype "passive"))
      (node (ref "R60") (pin "2") (pinfunction "2_2") (pintype "passive"))
      (node (ref "U$10") (pin "A13") (pinfunction "A13_A13") (pintype "bidirectional"))
    )
    (net (code "16") (name "/A13_TR_OUT1") (class "Default")
      (node (ref "R61") (pin "2") (pinfunction "2_2") (pintype "passive"))
      (node (ref "R63") (pin "2") (pinfunction "2_2") (pintype "passive"))
    )
    (net (code "17") (name "/A14_SW2") (class "Default")
      (node (ref "U$10") (pin "A14") (pinfunction "A14_A14") (pintype "bidirectional"))
    )
    (net (code "18") (name "/A16_LEDPWM3") (class "Default")
      (node (ref "U$10") (pin "A16") (pinfunction "A16_A16") (pintype "bidirectional"))
    )
    (net (code "19") (name "/A17_SW1") (class "Default")
      (node (ref "SW1") (pin "P3") (pinfunction "S_P3") (pintype "passive"))
      (node (ref "SW1") (pin "P4") (pinfunction "S_P4") (pintype "passive"))
      (node (ref "SW1") (pin "PL2") (pinfunction "C_PL2") (pintype "passive"))
      (node (ref "SW2") (pin "P3") (pinfunction "S_P3") (pintype "passive"))
      (node (ref "SW2") (pin "P4") (pinfunction "S_P4") (pintype "passive"))
      (node (ref "SW2") (pin "PL2") (pinfunction "C_PL2") (pintype "passive"))
      (node (ref "SW3") (pin "P3") (pinfunction "S_P3") (pintype "passive"))
      (node (ref "SW3") (pin "P4") (pinfunction "S_P4") (pintype "passive"))
      (node (ref "SW3") (pin "PL2") (pinfunction "C_PL2") (pintype "passive"))
      (node (ref "SW4") (pin "P3") (pinfunction "S_P3") (pintype "passive"))
      (node (ref "SW4") (pin "P4") (pinfunction "S_P4") (pintype "passive"))
      (node (ref "SW4") (pin "PL2") (pinfunction "C_PL2") (pintype "passive"))
      (node (ref "T1") (pin "C") (pinfunction "C_C") (pintype "passive"))
      (node (ref "T2") (pin "C") (pinfunction "C_C") (pintype "passive"))
      (node (ref "T3") (pin "C") (pinfunction "C_C") (pintype "passive"))
      (node (ref "T4") (pin "1") (pinfunction "C_1") (pintype "passive"))
      (node (ref "U$10") (pin "A17") (pinfunction "A17_A17") (pintype "bidirectional"))
    )
    (net (code "20") (name "/A18_ADC") (class "Default")
      (node (ref "C26") (pin "1") (pinfunction "1_1") (pintype "passive"))
      (node (ref "R68") (pin "2") (pinfunction "2_2") (pintype "passive"))
      (node (ref "U$10") (pin "A18") (pinfunction "A18_A18") (pintype "bidirectional"))
    )
    (net (code "21") (name "/A19_ADC") (class "Default")
      (node (ref "P1") (pin "2") (pinfunction "2_2") (pintype "bidirectional"))
      (node (ref "U$10") (pin "A19") (pinfunction "A19_A19") (pintype "bidirectional"))
    )
    (net (code "22") (name "/A20_ADC") (class "Default")
      (node (ref "C24") (pin "1") (pinfunction "1_1") (pintype "passive"))
      (node (ref "R57") (pin "2") (pinfunction "2_2") (pintype "passive"))
      (node (ref "U$10") (pin "A20") (pinfunction "A20_A20") (pintype "bidirectional"))
    )
    (net (code "23") (name "/A21_ADC") (class "Default")
      (node (ref "P2") (pin "2") (pinfunction "2_2") (pintype "bidirectional"))
      (node (ref "U$10") (pin "A21") (pinfunction "A21_A21") (pintype "bidirectional"))
    )
    (net (code "24") (name "/A22_DAC2") (class "Default")
      (node (ref "IC2") (pin "5") (pinfunction "+IN_5") (pintype "input"))
      (node (ref "U$10") (pin "A22") (pinfunction "A22_A22") (pintype "bidirectional"))
    )
    (net (code "25") (name "/A23_ADC") (class "Default")
      (node (ref "P5") (pin "2") (pinfunction "2_2") (pintype "bidirectional"))
      (node (ref "U$10") (pin "A23") (pinfunction "A23_A23") (pintype "bidirectional"))
    )
    (net (code "26") (name "/A24") (class "Default")
      (node (ref "U$10") (pin "A24") (pinfunction "A24_A24") (pintype "bidirectional"))
    )
    (net (code "27") (name "/A25_SW5") (class "Default")
      (node (ref "SW5") (pin "1") (pinfunction "S_1") (pintype "passive"))
      (node (ref "SW5") (pin "2") (pinfunction "S1_2") (pintype "passive"))
      (node (ref "U$10") (pin "A25") (pinfunction "A25_A25") (pintype "bidirectional"))
    )
    (net (code "28") (name "/AIN_A") (class "Default")
      (node (ref "C5") (pin "1") (pinfunction "1_1") (pintype "passive"))
      (node (ref "R13") (pin "1") (pinfunction "1_1") (pintype "passive"))
      (node (ref "R14") (pin "1") (pinfunction "1_1") (pintype "passive"))
      (node (ref "U$10") (pin "INA") (pinfunction "INA_INA") (pintype "bidirectional"))
    )
    (net (code "29") (name "/AIN_B") (class "Default")
      (node (ref "C6") (pin "1") (pinfunction "1_1") (pintype "passive"))
      (node (ref "R15") (pin "1") (pinfunction "1_1") (pintype "passive"))
      (node (ref "R16") (pin "1") (pinfunction "1_1") (pintype "passive"))
      (node (ref "U$10") (pin "INB") (pinfunction "INB_INB") (pintype "bidirectional"))
    )
    (net (code "30") (name "/AOUT_A+") (class "Default")
      (node (ref "R22") (pin "1") (pinfunction "1_1") (pintype "passive"))
      (node (ref "U$10") (pin "OUTA+") (pinfunction "OUTA+_OUTA+") (pintype "bidirectional"))
    )
    (net (code "31") (name "/AOUT_A-") (class "Default")
      (node (ref "R21") (pin "1") (pinfunction "1_1") (pintype "passive"))
      (node (ref "U$10") (pin "OUTA-") (pinfunction "OUTA-_OUTA-") (pintype "bidirectional"))
    )
    (net (code "32") (name "/AOUT_B+") (class "Default")
      (node (ref "R24") (pin "1") (pinfunction "1_1") (pintype "passive"))
      (node (ref "U$10") (pin "OUTB+") (pinfunction "OUTB+_OUTB+") (pintype "bidirectional"))
    )
    (net (code "33") (name "/AOUT_B-") (class "Default")
      (node (ref "R23") (pin "1") (pinfunction "1_1") (pintype "passive"))
      (node (ref "U$10") (pin "OUTB-") (pinfunction "OUTB-_OUTB-") (pintype "bidirectional"))
    )
    (net (code "34") (name "/B8_USBH_PWR_EN") (class "Default")
      (node (ref "U$10") (pin "B8") (pinfunction "B8_B8") (pintype "bidirectional"))
    )
    (net (code "35") (name "/B9_USBH_PWR_FAULT") (class "Default")
      (node (ref "U$10") (pin "B9") (pinfunction "B9_B9") (pintype "bidirectional"))
    )
    (net (code "36") (name "/BOOT0") (class "Default")
      (node (ref "BOOT") (pin "2") (pinfunction "2_2") (pintype "passive"))
      (node (ref "U$10") (pin "A15") (pinfunction "A15_A15") (pintype "bidirectional"))
    )
    (net (code "37") (name "/CS_VQ1") (class "Default")
      (node (ref "U$10") (pin "VQ1") (pinfunction "VQ1_VQ1") (pintype "bidirectional"))
    )
    (net (code "38") (name "/CS_VREF") (class "Default")
      (node (ref "C5") (pin "2") (pinfunction "2_2") (pintype "passive"))
      (node (ref "C6") (pin "2") (pinfunction "2_2") (pintype "passive"))
      (node (ref "R7") (pin "2") (pinfunction "2_2") (pintype "passive"))
      (node (ref "R8") (pin "2") (pinfunction "2_2") (pintype "passive"))
      (node (ref "U$10") (pin "VREF") (pinfunction "VREF_VREF") (pintype "bidirectional"))
    )
    (net (code "39") (name "/DC_IN_L") (class "Default")
      (node (ref "C1") (pin "+") (pinfunction "+_+") (pintype "passive"))
      (node (ref "IC1") (pin "3") (pinfunction "+IN_3") (pintype "input"))
      (node (ref "JP1") (pin "1") (pinfunction "1_1") (pintype "passive"))
      (node (ref "R7") (pin "1") (pinfunction "1_1") (pintype "passive"))
    )
    (net (code "40") (name "/DC_IN_R") (class "Default")
      (node (ref "C2") (pin "+") (pinfunction "+_+") (pintype "passive"))
      (node (ref "IC1") (pin "5") (pinfunction "+IN_5") (pintype "input"))
      (node (ref "JP1") (pin "2") (pinfunction "2_2") (pintype "passive"))
      (node (ref "R8") (pin "1") (pinfunction "1_1") (pintype "passive"))
    )
    (net (code "41") (name "/DC_OUT_L") (class "Default")
      (node (ref "JP2") (pin "1") (pinfunction "1_1") (pintype "passive"))
      (node (ref "R33") (pin "2") (pinfunction "2_2") (pintype "passive"))
    )
    (net (code "42") (name "/DC_OUT_R") (class "Default")
      (node (ref "JP2") (pin "2") (pinfunction "2_2") (pintype "passive"))
      (node (ref "R35") (pin "2") (pinfunction "2_2") (pintype "passive"))
    )
    (net (code "43") (name "/IN_L") (class "Default")
      (node (ref "C1") (pin "-") (pinfunction "-_-") (pintype "passive"))
      (node (ref "R5") (pin "1") (pinfunction "1_1") (pintype "passive"))
      (node (ref "U$4") (pin "P$3") (pinfunction "P1_P$3") (pintype "bidirectional"))
    )
    (net (code "44") (name "/IN_R") (class "Default")
      (node (ref "C2") (pin "-") (pinfunction "-_-") (pintype "passive"))
      (node (ref "R6") (pin "1") (pinfunction "1_1") (pintype "passive"))
      (node (ref "U$4") (pin "P$2") (pinfunction "P2_P$2") (pintype "bidirectional"))
    )
    (net (code "45") (name "/OUT_L") (class "Default")
      (node (ref "R34") (pin "2") (pinfunction "2_2") (pintype "passive"))
      (node (ref "R37") (pin "1") (pinfunction "1_1") (pintype "passive"))
      (node (ref "U$5") (pin "P$3") (pinfunction "P1_P$3") (pintype "bidirectional"))
    )
    (net (code "46") (name "/OUT_R") (class "Default")
      (node (ref "R36") (pin "2") (pinfunction "2_2") (pintype "passive"))
      (node (ref "R38") (pin "1") (pinfunction "1_1") (pintype "passive"))
      (node (ref "U$5") (pin "P$2") (pinfunction "P2_P$2") (pintype "bidirectional"))
    )
    (net (code "47") (name "/USBD_DM") (class "Default")
      (node (ref "U$10") (pin "USBD_DM") (pinfunction "USBD_DM_USBD_DM") (pintype "bidirectional"))
      (node (ref "X5") (pin "D-") (pinfunction "D-_D-") (pintype "bidirectional"))
    )
    (net (code "48") (name "/USBD_DP") (class "Default")
      (node (ref "U$10") (pin "USBD_DP") (pinfunction "USBD_DP_USBD_DP") (pintype "bidirectional"))
      (node (ref "X5") (pin "D+") (pinfunction "D+_D+") (pintype "bidirectional"))
    )
    (net (code "49") (name "/USBD_ID") (class "Default")
      (node (ref "U$10") (pin "USBD_ID") (pinfunction "USBD_ID_USBD_ID") (pintype "bidirectional"))
    )
    (net (code "50") (name "/USBD_VBUS") (class "Default")
      (node (ref "U$10") (pin "USBD_VBUS") (pinfunction "USBD_VBUS_USBD_VBUS") (pintype "bidirectional"))
      (node (ref "VBUS") (pin "1") (pinfunction "1_1") (pintype "passive"))
      (node (ref "X5") (pin "VBUS") (pinfunction "VBUS_VBUS") (pintype "bidirectional"))
    )
    (net (code "51") (name "/USBH_DM") (class "Default")
      (node (ref "U$10") (pin "USBH_DM") (pinfunction "USBH_DM_USBH_DM") (pintype "bidirectional"))
      (node (ref "X3") (pin "2") (pinfunction "2_2") (pintype "passive"))
    )
    (net (code "52") (name "/USBH_DP") (class "Default")
      (node (ref "U$10") (pin "USBH_DP") (pinfunction "USBH_DP_USBH_DP") (pintype "bidirectional"))
      (node (ref "X3") (pin "3") (pinfunction "3_3") (pintype "passive"))
    )
    (net (code "53") (name "/USBH_VBUS") (class "Default")
      (node (ref "C25") (pin "2") (pinfunction "2_2") (pintype "passive"))
      (node (ref "F1") (pin "P$2") (pinfunction "2_P$2") (pintype "bidirectional"))
      (node (ref "X3") (pin "1") (pinfunction "1_1") (pintype "passive"))
    )
    (net (code "54") (name "GND") (class "Default")
      (node (ref "BOOT") (pin "1") (pinfunction "1_1") (pintype "passive"))
      (node (ref "C10") (pin "2") (pinfunction "2_2") (pintype "passive"))
      (node (ref "C11") (pin "2") (pinfunction "2_2") (pintype "passive"))
      (node (ref "C12") (pin "2") (pinfunction "2_2") (pintype "passive"))
      (node (ref "C14") (pin "-") (pinfunction "-_-") (pintype "passive"))
      (node (ref "C15") (pin "-") (pinfunction "-_-") (pintype "passive"))
      (node (ref "C19") (pin "1") (pinfunction "1_1") (pintype "passive"))
      (node (ref "C20") (pin "1") (pinfunction "1_1") (pintype "passive"))
      (node (ref "C23") (pin "2") (pinfunction "2_2") (pintype "passive"))
      (node (ref "C24") (pin "2") (pinfunction "2_2") (pintype "passive"))
      (node (ref "C25") (pin "1") (pinfunction "1_1") (pintype "passive"))
      (node (ref "C26") (pin "2") (pinfunction "2_2") (pintype "passive"))
      (node (ref "C27") (pin "2") (pinfunction "2_2") (pintype "passive"))
      (node (ref "C28") (pin "2") (pinfunction "2_2") (pintype "passive"))
      (node (ref "C9") (pin "2") (pinfunction "2_2") (pintype "passive"))
      (node (ref "D3") (pin "A") (pinfunction "A_A") (pintype "passive"))
      (node (ref "D5") (pin "A") (pinfunction "A_A") (pintype "passive"))
      (node (ref "D7") (pin "A") (pinfunction "A_A") (pintype "passive"))
      (node (ref "D9") (pin "A") (pinfunction "A_A") (pintype "passive"))
      (node (ref "IC1") (pin "11") (pinfunction "V-_11") (pintype "power_in"))
      (node (ref "IC2") (pin "4") (pinfunction "V-_4") (pintype "power_in"))
      (node (ref "J1") (pin "P$1") (pinfunction "5_P$1") (pintype "passive"))
      (node (ref "J1") (pin "P$2") (pinfunction "4_P$2") (pintype "passive"))
      (node (ref "J10") (pin "P$1") (pinfunction "5_P$1") (pintype "passive"))
      (node (ref "J11") (pin "P$1") (pinfunction "5_P$1") (pintype "passive"))
      (node (ref "J11") (pin "P$2") (pinfunction "4_P$2") (pintype "passive"))
      (node (ref "J12") (pin "P$1") (pinfunction "5_P$1") (pintype "passive"))
      (node (ref "J12") (pin "P$2") (pinfunction "4_P$2") (pintype "passive"))
      (node (ref "J13") (pin "P$1") (pinfunction "5_P$1") (pintype "passive"))
      (node (ref "J13") (pin "P$2") (pinfunction "4_P$2") (pintype "passive"))
      (node (ref "J2") (pin "P$1") (pinfunction "5_P$1") (pintype "passive"))
      (node (ref "J3") (pin "P$1") (pinfunction "5_P$1") (pintype "passive"))
      (node (ref "J3") (pin "P$2") (pinfunction "4_P$2") (pintype "passive"))
      (node (ref "J4") (pin "P$1") (pinfunction "5_P$1") (pintype "passive"))
      (node (ref "J4") (pin "P$2") (pinfunction "4_P$2") (pintype "passive"))
      (node (ref "J5") (pin "P$1") (pinfunction "5_P$1") (pintype "passive"))
      (node (ref "J5") (pin "P$2") (pinfunction "4_P$2") (pintype "passive"))
      (node (ref "J6") (pin "P$1") (pinfunction "5_P$1") (pintype "passive"))
      (node (ref "J6") (pin "P$2") (pinfunction "4_P$2") (pintype "passive"))
      (node (ref "J8") (pin "P$1") (pinfunction "5_P$1") (pintype "passive"))
      (node (ref "J9") (pin "P$1") (pinfunction "5_P$1") (pintype "passive"))
      (node (ref "JP1") (pin "3") (pinfunction "3_3") (pintype "passive"))
      (node (ref "JP2") (pin "3") (pinfunction "3_3") (pintype "passive"))
      (node (ref "P1") (pin "1") (pinfunction "1_1") (pintype "bidirectional"))
      (node (ref "P1") (pin "P$5") (pinfunction "P$1_P$5") (pintype "bidirectional"))
      (node (ref "P1") (pin "P$6") (pinfunction "P$1_P$6") (pintype "bidirectional"))
      (node (ref "P2") (pin "1") (pinfunction "1_1") (pintype "bidirectional"))
      (node (ref "P2") (pin "P$5") (pinfunction "P$1_P$5") (pintype "bidirectional"))
      (node (ref "P2") (pin "P$6") (pinfunction "P$1_P$6") (pintype "bidirectional"))
      (node (ref "P3") (pin "1") (pinfunction "1_1") (pintype "bidirectional"))
      (node (ref "P3") (pin "P$5") (pinfunction "P$1_P$5") (pintype "bidirectional"))
      (node (ref "P3") (pin "P$6") (pinfunction "P$1_P$6") (pintype "bidirectional"))
      (node (ref "P4") (pin "1") (pinfunction "1_1") (pintype "bidirectional"))
      (node (ref "P4") (pin "P$5") (pinfunction "P$1_P$5") (pintype "bidirectional"))
      (node (ref "P4") (pin "P$6") (pinfunction "P$1_P$6") (pintype "bidirectional"))
      (node (ref "P5") (pin "1") (pinfunction "1_1") (pintype "bidirectional"))
      (node (ref "P5") (pin "P$5") (pinfunction "P$1_P$5") (pintype "bidirectional"))
      (node (ref "P5") (pin "P$6") (pinfunction "P$1_P$6") (pintype "bidirectional"))
      (node (ref "R2") (pin "1") (pinfunction "1_1") (pintype "passive"))
      (node (ref "R20") (pin "1") (pinfunction "1_1") (pintype "passive"))
      (node (ref "R37") (pin "2") (pinfunction "2_2") (pintype "passive"))
      (node (ref "R38") (pin "2") (pinfunction "2_2") (pintype "passive"))
      (node (ref "R45") (pin "1") (pinfunction "1_1") (pintype "passive"))
      (node (ref "R48") (pin "1") (pinfunction "1_1") (pintype "passive"))
      (node (ref "R5") (pin "2") (pinfunction "2_2") (pintype "passive"))
      (node (ref "R58") (pin "2") (pinfunction "2_2") (pintype "passive"))
      (node (ref "R59") (pin "2") (pinfunction "2_2") (pintype "passive"))
      (node (ref "R6") (pin "2") (pinfunction "2_2") (pintype "passive"))
      (node (ref "R64") (pin "1") (pinfunction "1_1") (pintype "passive"))
      (node (ref "R65") (pin "1") (pinfunction "1_1") (pintype "passive"))
      (node (ref "R70") (pin "2") (pinfunction "2_2") (pintype "passive"))
      (node (ref "R73") (pin "2") (pinfunction "2_2") (pintype "passive"))
      (node (ref "SW1") (pin "P1") (pinfunction "P_P1") (pintype "passive"))
      (node (ref "SW1") (pin "P2") (pinfunction "P_P2") (pintype "passive"))
      (node (ref "SW2") (pin "P1") (pinfunction "P_P1") (pintype "passive"))
      (node (ref "SW2") (pin "P2") (pinfunction "P_P2") (pintype "passive"))
      (node (ref "SW3") (pin "P1") (pinfunction "P_P1") (pintype "passive"))
      (node (ref "SW3") (pin "P2") (pinfunction "P_P2") (pintype "passive"))
      (node (ref "SW4") (pin "P1") (pinfunction "P_P1") (pintype "passive"))
      (node (ref "SW4") (pin "P2") (pinfunction "P_P2") (pintype "passive"))
      (node (ref "SW5") (pin "3") (pinfunction "P_3") (pintype "passive"))
      (node (ref "SW5") (pin "4") (pinfunction "P1_4") (pintype "passive"))
      (node (ref "T1") (pin "E") (pinfunction "E_E") (pintype "passive"))
      (node (ref "T2") (pin "E") (pinfunction "E_E") (pintype "passive"))
      (node (ref "T3") (pin "E") (pinfunction "E_E") (pintype "passive"))
      (node (ref "T4") (pin "3") (pinfunction "E_3") (pintype "passive"))
      (node (ref "T5") (pin "E") (pinfunction "E_E") (pintype "passive"))
      (node (ref "T6") (pin "E") (pinfunction "E_E") (pintype "passive"))
      (node (ref "U$10") (pin "GND") (pinfunction "GND_GND") (pintype "bidirectional"))
      (node (ref "U$10") (pin "GND_2") (pinfunction "GND_GND_2") (pintype "bidirectional"))
      (node (ref "U$10") (pin "GND_3") (pinfunction "GND_GND_3") (pintype "bidirectional"))
      (node (ref "U$10") (pin "GND_4") (pinfunction "GND_GND_4") (pintype "bidirectional"))
      (node (ref "U$4") (pin "P$1") (pinfunction "P3_P$1") (pintype "bidirectional"))
      (node (ref "U$5") (pin "P$1") (pinfunction "P3_P$1") (pintype "bidirectional"))
      (node (ref "X3") (pin "4") (pinfunction "4_4") (pintype "passive"))
      (node (ref "X5") (pin "GND") (pinfunction "GND_GND") (pintype "bidirectional"))
    )
    (net (code "55") (name "Net-(C9-Pad1)") (class "Default")
      (node (ref "C9") (pin "1") (pinfunction "1_1") (pintype "passive"))
      (node (ref "R21") (pin "2") (pinfunction "2_2") (pintype "passive"))
      (node (ref "R25") (pin "1") (pinfunction "1_1") (pintype "passive"))
      (node (ref "R26") (pin "1") (pinfunction "1_1") (pintype "passive"))
    )
    (net (code "56") (name "Net-(C10-Pad1)") (class "Default")
      (node (ref "C10") (pin "1") (pinfunction "1_1") (pintype "passive"))
      (node (ref "R22") (pin "2") (pinfunction "2_2") (pintype "passive"))
      (node (ref "R27") (pin "1") (pinfunction "1_1") (pintype "passive"))
      (node (ref "R28") (pin "2") (pinfunction "2_2") (pintype "passive"))
    )
    (net (code "57") (name "Net-(C11-Pad1)") (class "Default")
      (node (ref "C11") (pin "1") (pinfunction "1_1") (pintype "passive"))
      (node (ref "R23") (pin "2") (pinfunction "2_2") (pintype "passive"))
      (node (ref "R29") (pin "1") (pinfunction "1_1") (pintype "passive"))
      (node (ref "R30") (pin "1") (pinfunction "1_1") (pintype "passive"))
    )
    (net (code "58") (name "Net-(C12-Pad1)") (class "Default")
      (node (ref "C12") (pin "1") (pinfunction "1_1") (pintype "passive"))
      (node (ref "R24") (pin "2") (pinfunction "2_2") (pintype "passive"))
      (node (ref "R31") (pin "1") (pinfunction "1_1") (pintype "passive"))
      (node (ref "R32") (pin "2") (pinfunction "2_2") (pintype "passive"))
    )
    (net (code "59") (name "Net-(C14-Pad+)") (class "Default")
      (node (ref "C14") (pin "+") (pinfunction "+_+") (pintype "passive"))
      (node (ref "R28") (pin "1") (pinfunction "1_1") (pintype "passive"))
    )
    (net (code "60") (name "Net-(C15-Pad+)") (class "Default")
      (node (ref "C15") (pin "+") (pinfunction "+_+") (pintype "passive"))
      (node (ref "R32") (pin "1") (pinfunction "1_1") (pintype "passive"))
    )
    (net (code "61") (name "Net-(C21-Pad-)") (class "Default")
      (node (ref "C21") (pin "-") (pinfunction "-_-") (pintype "passive"))
      (node (ref "R34") (pin "1") (pinfunction "1_1") (pintype "passive"))
    )
    (net (code "62") (name "Net-(C22-Pad-)") (class "Default")
      (node (ref "C22") (pin "-") (pinfunction "-_-") (pintype "passive"))
      (node (ref "R36") (pin "1") (pinfunction "1_1") (pintype "passive"))
    )
    (net (code "63") (name "Net-(D2-PadA)") (class "Default")
      (node (ref "D2") (pin "A") (pinfunction "A_A") (pintype "passive"))
      (node (ref "D3") (pin "C") (pinfunction "C_C") (pintype "passive"))
      (node (ref "R42") (pin "2") (pinfunction "2_2") (pintype "passive"))
      (node (ref "R58") (pin "1") (pinfunction "1_1") (pintype "passive"))
      (node (ref "R68") (pin "1") (pinfunction "1_1") (pintype "passive"))
    )
    (net (code "64") (name "Net-(D4-PadA)") (class "Default")
      (node (ref "D4") (pin "A") (pinfunction "A_A") (pintype "passive"))
      (node (ref "D5") (pin "C") (pinfunction "C_C") (pintype "passive"))
      (node (ref "R41") (pin "2") (pinfunction "2_2") (pintype "passive"))
      (node (ref "R57") (pin "1") (pinfunction "1_1") (pintype "passive"))
      (node (ref "R59") (pin "1") (pinfunction "1_1") (pintype "passive"))
    )
    (net (code "65") (name "Net-(D6-PadA)") (class "Default")
      (node (ref "D6") (pin "A") (pinfunction "A_A") (pintype "passive"))
      (node (ref "D7") (pin "C") (pinfunction "C_C") (pintype "passive"))
      (node (ref "R69") (pin "2") (pinfunction "2_2") (pintype "passive"))
      (node (ref "R70") (pin "1") (pinfunction "1_1") (pintype "passive"))
      (node (ref "R71") (pin "1") (pinfunction "1_1") (pintype "passive"))
    )
    (net (code "66") (name "Net-(D8-PadA)") (class "Default")
      (node (ref "D8") (pin "A") (pinfunction "A_A") (pintype "passive"))
      (node (ref "D9") (pin "C") (pinfunction "C_C") (pintype "passive"))
      (node (ref "R72") (pin "2") (pinfunction "2_2") (pintype "passive"))
      (node (ref "R73") (pin "1") (pinfunction "1_1") (pintype "passive"))
      (node (ref "R74") (pin "1") (pinfunction "1_1") (pintype "passive"))
    )
    (net (code "67") (name "Net-(IC1A--IN)") (class "Default")
      (node (ref "C3") (pin "1") (pinfunction "1_1") (pintype "passive"))
      (node (ref "IC1") (pin "2") (pinfunction "-IN_2") (pintype "input"))
      (node (ref "R13") (pin "2") (pinfunction "2_2") (pintype "passive"))
    )
    (net (code "68") (name "Net-(IC1A-OUT)") (class "Default")
      (node (ref "C3") (pin "2") (pinfunction "2_2") (pintype "passive"))
      (node (ref "IC1") (pin "1") (pinfunction "OUT_1") (pintype "output"))
      (node (ref "R14") (pin "2") (pinfunction "2_2") (pintype "passive"))
    )
    (net (code "69") (name "Net-(IC1B--IN)") (class "Default")
      (node (ref "C4") (pin "1") (pinfunction "1_1") (pintype "passive"))
      (node (ref "IC1") (pin "6") (pinfunction "-IN_6") (pintype "input"))
      (node (ref "R15") (pin "2") (pinfunction "2_2") (pintype "passive"))
    )
    (net (code "70") (name "Net-(IC1B-OUT)") (class "Default")
      (node (ref "C4") (pin "2") (pinfunction "2_2") (pintype "passive"))
      (node (ref "IC1") (pin "7") (pinfunction "OUT_7") (pintype "output"))
      (node (ref "R16") (pin "2") (pinfunction "2_2") (pintype "passive"))
    )
    (net (code "71") (name "Net-(IC1C-+IN)") (class "Default")
      (node (ref "C19") (pin "2") (pinfunction "2_2") (pintype "passive"))
      (node (ref "IC1") (pin "10") (pinfunction "+IN_10") (pintype "input"))
      (node (ref "R27") (pin "2") (pinfunction "2_2") (pintype "passive"))
    )
    (net (code "72") (name "Net-(IC1C--IN)") (class "Default")
      (node (ref "C17") (pin "1") (pinfunction "1_1") (pintype "passive"))
      (node (ref "IC1") (pin "9") (pinfunction "-IN_9") (pintype "input"))
      (node (ref "R26") (pin "2") (pinfunction "2_2") (pintype "passive"))
    )
    (net (code "73") (name "Net-(IC1C-OUT)") (class "Default")
      (node (ref "C17") (pin "2") (pinfunction "2_2") (pintype "passive"))
      (node (ref "C21") (pin "+") (pinfunction "+_+") (pintype "passive"))
      (node (ref "IC1") (pin "8") (pinfunction "OUT_8") (pintype "output"))
      (node (ref "R25") (pin "2") (pinfunction "2_2") (pintype "passive"))
      (node (ref "R33") (pin "1") (pinfunction "1_1") (pintype "passive"))
    )
    (net (code "74") (name "Net-(IC1D-+IN)") (class "Default")
      (node (ref "C20") (pin "2") (pinfunction "2_2") (pintype "passive"))
      (node (ref "IC1") (pin "12") (pinfunction "+IN_12") (pintype "input"))
      (node (ref "R31") (pin "2") (pinfunction "2_2") (pintype "passive"))
    )
    (net (code "75") (name "Net-(IC1D--IN)") (class "Default")
      (node (ref "C18") (pin "1") (pinfunction "1_1") (pintype "passive"))
      (node (ref "IC1") (pin "13") (pinfunction "-IN_13") (pintype "input"))
      (node (ref "R30") (pin "2") (pinfunction "2_2") (pintype "passive"))
    )
    (net (code "76") (name "Net-(IC1D-OUT)") (class "Default")
      (node (ref "C18") (pin "2") (pinfunction "2_2") (pintype "passive"))
      (node (ref "C22") (pin "+") (pinfunction "+_+") (pintype "passive"))
      (node (ref "IC1") (pin "14") (pinfunction "OUT_14") (pintype "output"))
      (node (ref "R29") (pin "2") (pinfunction "2_2") (pintype "passive"))
      (node (ref "R35") (pin "1") (pinfunction "1_1") (pintype "passive"))
    )
    (net (code "77") (name "Net-(IC2A--IN)") (class "Default")
      (node (ref "IC2") (pin "2") (pinfunction "-IN_2") (pintype "input"))
      (node (ref "R18") (pin "1") (pinfunction "1_1") (pintype "passive"))
      (node (ref "R64") (pin "2") (pinfunction "2_2") (pintype "passive"))
    )
    (net (code "78") (name "Net-(IC2A-OUT)") (class "Default")
      (node (ref "IC2") (pin "1") (pinfunction "OUT_1") (pintype "output"))
      (node (ref "R17") (pin "1") (pinfunction "1_1") (pintype "passive"))
      (node (ref "R18") (pin "2") (pinfunction "2_2") (pintype "passive"))
    )
    (net (code "79") (name "Net-(IC2B--IN)") (class "Default")
      (node (ref "IC2") (pin "6") (pinfunction "-IN_6") (pintype "input"))
      (node (ref "R65") (pin "2") (pinfunction "2_2") (pintype "passive"))
      (node (ref "R66") (pin "2") (pinfunction "2_2") (pintype "passive"))
    )
    (net (code "80") (name "Net-(IC2B-OUT)") (class "Default")
      (node (ref "IC2") (pin "7") (pinfunction "OUT_7") (pintype "output"))
      (node (ref "R66") (pin "1") (pinfunction "1_1") (pintype "passive"))
      (node (ref "R67") (pin "1") (pinfunction "1_1") (pintype "passive"))
    )
    (net (code "81") (name "Net-(J1-3)") (class "Default")
      (node (ref "J1") (pin "P$3") (pinfunction "3_P$3") (pintype "passive"))
      (node (ref "R42") (pin "1") (pinfunction "1_1") (pintype "passive"))
    )
    (net (code "82") (name "Net-(J2-3)") (class "Default")
      (node (ref "J2") (pin "P$3") (pinfunction "3_P$3") (pintype "passive"))
      (node (ref "R1") (pin "1") (pinfunction "1_1") (pintype "passive"))
    )
    (net (code "83") (name "Net-(J3-3)") (class "Default")
      (node (ref "J3") (pin "P$3") (pinfunction "3_P$3") (pintype "passive"))
      (node (ref "R41") (pin "1") (pinfunction "1_1") (pintype "passive"))
    )
    (net (code "84") (name "Net-(J4-3)") (class "Default")
      (node (ref "J4") (pin "P$3") (pinfunction "3_P$3") (pintype "passive"))
      (node (ref "R17") (pin "2") (pinfunction "2_2") (pintype "passive"))
    )
    (net (code "85") (name "Net-(J5-3)") (class "Default")
      (node (ref "J5") (pin "P$3") (pinfunction "3_P$3") (pintype "passive"))
      (node (ref "R12") (pin "1") (pinfunction "1_1") (pintype "passive"))
    )
    (net (code "86") (name "Net-(J6-3)") (class "Default")
      (node (ref "J6") (pin "P$3") (pinfunction "3_P$3") (pintype "passive"))
      (node (ref "R67") (pin "2") (pinfunction "2_2") (pintype "passive"))
    )
    (net (code "87") (name "Net-(J8-3)") (class "Default")
      (node (ref "J8") (pin "P$3") (pinfunction "3_P$3") (pintype "passive"))
      (node (ref "R19") (pin "1") (pinfunction "1_1") (pintype "passive"))
    )
    (net (code "88") (name "Net-(J9-3)") (class "Default")
      (node (ref "J9") (pin "P$3") (pinfunction "3_P$3") (pintype "passive"))
      (node (ref "R44") (pin "1") (pinfunction "1_1") (pintype "passive"))
    )
    (net (code "89") (name "Net-(J10-3)") (class "Default")
      (node (ref "J10") (pin "P$3") (pinfunction "3_P$3") (pintype "passive"))
      (node (ref "R47") (pin "1") (pinfunction "1_1") (pintype "passive"))
    )
    (net (code "90") (name "Net-(J11-3)") (class "Default")
      (node (ref "J11") (pin "P$3") (pinfunction "3_P$3") (pintype "passive"))
      (node (ref "R39") (pin "1") (pinfunction "1_1") (pintype "passive"))
    )
    (net (code "91") (name "Net-(J12-3)") (class "Default")
      (node (ref "J12") (pin "P$3") (pinfunction "3_P$3") (pintype "passive"))
      (node (ref "R72") (pin "1") (pinfunction "1_1") (pintype "passive"))
    )
    (net (code "92") (name "Net-(J13-3)") (class "Default")
      (node (ref "J13") (pin "P$3") (pinfunction "3_P$3") (pintype "passive"))
      (node (ref "R69") (pin "1") (pinfunction "1_1") (pintype "passive"))
    )
    (net (code "93") (name "Net-(JP1-Pad5)") (class "Default")
      (node (ref "JP1") (pin "5") (pinfunction "5_5") (pintype "passive"))
      (node (ref "R3") (pin "2") (pinfunction "2_2") (pintype "passive"))
    )
    (net (code "94") (name "Net-(LED2-PadA)") (class "Default")
      (node (ref "LED2") (pin "A") (pinfunction "A_A") (pintype "passive"))
      (node (ref "R50") (pin "2") (pinfunction "2_2") (pintype "passive"))
    )
    (net (code "95") (name "Net-(LED3-PadA)") (class "Default")
      (node (ref "LED3") (pin "A") (pinfunction "A_A") (pintype "passive"))
      (node (ref "R75") (pin "2") (pinfunction "2_2") (pintype "passive"))
    )
    (net (code "96") (name "Net-(LED4-PadA)") (class "Default")
      (node (ref "LED4") (pin "A") (pinfunction "A_A") (pintype "passive"))
      (node (ref "R76") (pin "2") (pinfunction "2_2") (pintype "passive"))
    )
    (net (code "97") (name "Net-(LED5-PadA)") (class "Default")
      (node (ref "LED5") (pin "A") (pinfunction "A_A") (pintype "passive"))
      (node (ref "R77") (pin "2") (pinfunction "2_2") (pintype "passive"))
    )
    (net (code "98") (name "Net-(LED6-C)") (class "Default")
      (node (ref "LED6") (pin "K") (pinfunction "C_K") (pintype "passive"))
      (node (ref "R60") (pin "1") (pinfunction "1_1") (pintype "passive"))
    )
    (net (code "99") (name "Net-(LED7-C)") (class "Default")
      (node (ref "LED7") (pin "K") (pinfunction "C_K") (pintype "passive"))
      (node (ref "R63") (pin "1") (pinfunction "1_1") (pintype "passive"))
    )
    (net (code "100") (name "Net-(LED8-C)") (class "Default")
      (node (ref "LED8") (pin "K") (pinfunction "C_K") (pintype "passive"))
      (node (ref "R10") (pin "2") (pinfunction "2_2") (pintype "passive"))
    )
    (net (code "101") (name "Net-(LED9-C)") (class "Default")
      (node (ref "LED9") (pin "K") (pinfunction "C_K") (pintype "passive"))
      (node (ref "R9") (pin "2") (pinfunction "2_2") (pintype "passive"))
    )
    (net (code "102") (name "Net-(R1-Pad2)") (class "Default")
      (node (ref "R1") (pin "2") (pinfunction "2_2") (pintype "passive"))
      (node (ref "R2") (pin "2") (pinfunction "2_2") (pintype "passive"))
      (node (ref "T1") (pin "B") (pinfunction "B_B") (pintype "passive"))
    )
    (net (code "103") (name "Net-(R12-Pad2)") (class "Default")
      (node (ref "R12") (pin "2") (pinfunction "2_2") (pintype "passive"))
      (node (ref "R40") (pin "2") (pinfunction "2_2") (pintype "passive"))
      (node (ref "T5") (pin "C") (pinfunction "C_C") (pintype "passive"))
    )
    (net (code "104") (name "Net-(R19-Pad2)") (class "Default")
      (node (ref "R19") (pin "2") (pinfunction "2_2") (pintype "passive"))
      (node (ref "R20") (pin "2") (pinfunction "2_2") (pintype "passive"))
      (node (ref "T2") (pin "B") (pinfunction "B_B") (pintype "passive"))
    )
    (net (code "105") (name "Net-(R39-Pad2)") (class "Default")
      (node (ref "R39") (pin "2") (pinfunction "2_2") (pintype "passive"))
      (node (ref "R54") (pin "2") (pinfunction "2_2") (pintype "passive"))
      (node (ref "T6") (pin "C") (pinfunction "C_C") (pintype "passive"))
    )
    (net (code "106") (name "Net-(R44-Pad2)") (class "Default")
      (node (ref "R44") (pin "2") (pinfunction "2_2") (pintype "passive"))
      (node (ref "R45") (pin "2") (pinfunction "2_2") (pintype "passive"))
      (node (ref "T3") (pin "B") (pinfunction "B_B") (pintype "passive"))
    )
    (net (code "107") (name "Net-(R55-Pad1)") (class "Default")
      (node (ref "R55") (pin "1") (pinfunction "1_1") (pintype "passive"))
      (node (ref "T5") (pin "B") (pinfunction "B_B") (pintype "passive"))
    )
    (net (code "108") (name "Net-(R61-Pad1)") (class "Default")
      (node (ref "R61") (pin "1") (pinfunction "1_1") (pintype "passive"))
      (node (ref "T6") (pin "B") (pinfunction "B_B") (pintype "passive"))
    )
    (net (code "109") (name "Net-(SW1B-A)") (class "Default")
      (node (ref "R4") (pin "2") (pinfunction "2_2") (pintype "passive"))
      (node (ref "SW1") (pin "PL1") (pinfunction "A_PL1") (pintype "passive"))
    )
    (net (code "110") (name "Net-(SW2B-A)") (class "Default")
      (node (ref "R43") (pin "2") (pinfunction "2_2") (pintype "passive"))
      (node (ref "SW2") (pin "PL1") (pinfunction "A_PL1") (pintype "passive"))
    )
    (net (code "111") (name "Net-(SW3B-A)") (class "Default")
      (node (ref "R46") (pin "2") (pinfunction "2_2") (pintype "passive"))
      (node (ref "SW3") (pin "PL1") (pinfunction "A_PL1") (pintype "passive"))
    )
    (net (code "112") (name "Net-(SW4B-A)") (class "Default")
      (node (ref "R49") (pin "2") (pinfunction "2_2") (pintype "passive"))
      (node (ref "SW4") (pin "PL1") (pinfunction "A_PL1") (pintype "passive"))
    )
    (net (code "113") (name "Net-(T4-B)") (class "Default")
      (node (ref "R47") (pin "2") (pinfunction "2_2") (pintype "passive"))
      (node (ref "R48") (pin "2") (pinfunction "2_2") (pintype "passive"))
      (node (ref "T4") (pin "2") (pinfunction "B_2") (pintype "passive"))
    )
    (net (code "114") (name "unconnected-(J2-4-PadP$2)") (class "Default")
      (node (ref "J2") (pin "P$2") (pinfunction "4_P$2") (pintype "passive"))
    )
    (net (code "115") (name "unconnected-(J8-4-PadP$2)") (class "Default")
      (node (ref "J8") (pin "P$2") (pinfunction "4_P$2") (pintype "passive"))
    )
    (net (code "116") (name "unconnected-(J9-4-PadP$2)") (class "Default")
      (node (ref "J9") (pin "P$2") (pinfunction "4_P$2") (pintype "passive"))
    )
    (net (code "117") (name "unconnected-(J10-4-PadP$2)") (class "Default")
      (node (ref "J10") (pin "P$2") (pinfunction "4_P$2") (pintype "passive"))
    )
    (net (code "118") (name "unconnected-(U$10-PadUSBH_ID)") (class "Default")
      (node (ref "U$10") (pin "USBH_ID") (pinfunction "USBH_ID_USBH_ID") (pintype "bidirectional"))
    )
    (net (code "119") (name "unconnected-(U$10-PadUSBH_VBUS)") (class "Default")
      (node (ref "U$10") (pin "USBH_VBUS") (pinfunction "USBH_VBUS_USBH_VBUS") (pintype "bidirectional"))
    )
    (net (code "120") (name "unconnected-(X3-S1-PadM1)") (class "Default")
      (node (ref "X3") (pin "M1") (pinfunction "S1_M1") (pintype "passive"))
    )
    (net (code "121") (name "unconnected-(X3-S2-PadM2)") (class "Default")
      (node (ref "X3") (pin "M2") (pinfunction "S2_M2") (pintype "passive"))
    )
  )
)
